# 1-wire_board.net
KiCad netlist of a schematic drawn in EAGLE
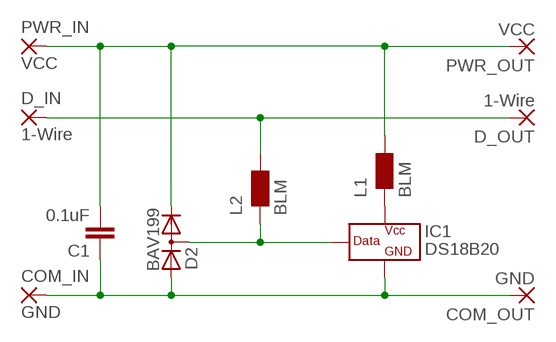
[diagram p0: schematic, sheet 1]

(export (version "E")
  (design (tool "Eeschema 10.0.6"))
  (components
    (comp (ref "C1")
      (value "0.1uF")
      (footprint "eagle-import:0805")
      (libsource (lib "eagle-import") (part "CAP0805"))
    )
    (comp (ref "COM_IN")
      (value "GND")
      (footprint "eagle-import:SMD2,54-5,08")
      (libsource (lib "eagle-import") (part "SMD5"))
    )
    (comp (ref "COM_OUT")
      (value "GND")
      (footprint "eagle-import:SMD2,54-5,08")
      (libsource (lib "eagle-import") (part "SMD5"))
    )
    (comp (ref "D2")
      (value "BAV199")
      (footprint "eagle-import:SOT23")
      (libsource (lib "eagle-import") (part "BAV199"))
    )
    (comp (ref "D_IN")
      (value "1-Wire")
      (footprint "eagle-import:SMD2,54-5,08")
      (libsource (lib "eagle-import") (part "SMD5"))
    )
    (comp (ref "D_OUT")
      (value "1-Wire")
      (footprint "eagle-import:SMD2,54-5,08")
      (libsource (lib "eagle-import") (part "SMD5"))
    )
    (comp (ref "IC1")
      (value "DS18B20")
      (footprint "eagle-import:TO92-")
      (libsource (lib "eagle-import") (part "DS18B20"))
    )
    (comp (ref "L1")
      (value "BLM")
      (footprint "eagle-import:0805")
      (libsource (lib "eagle-import") (part "WE-KIHQWE-KI_0805"))
    )
    (comp (ref "L2")
      (value "BLM")
      (footprint "eagle-import:0805")
      (libsource (lib "eagle-import") (part "WE-KIHQWE-KI_0805"))
    )
    (comp (ref "PWR_IN")
      (value "VCC")
      (footprint "eagle-import:SMD2,54-5,08")
      (libsource (lib "eagle-import") (part "SMD5"))
    )
    (comp (ref "PWR_OUT")
      (value "VCC")
      (footprint "eagle-import:SMD2,54-5,08")
      (libsource (lib "eagle-import") (part "SMD5"))
    )
  )
  (nets
    (net (code "1") (name "Net-(COM_IN-P)") (class "Default")
      (node (ref "C1") (pin "1") (pinfunction "1_1") (pintype "passive"))
      (node (ref "COM_IN") (pin "1") (pinfunction "P_1") (pintype "passive"))
      (node (ref "COM_OUT") (pin "1") (pinfunction "P_1") (pintype "passive"))
      (node (ref "D2") (pin "1") (pinfunction "A_1") (pintype "passive"))
      (node (ref "IC1") (pin "1") (pinfunction "GND_1") (pintype "bidirectional"))
    )
    (net (code "2") (name "Net-(D2-AC)") (class "Default")
      (node (ref "D2") (pin "3") (pinfunction "AC_3") (pintype "passive"))
      (node (ref "IC1") (pin "2") (pinfunction "DATA_2") (pintype "bidirectional"))
      (node (ref "L2") (pin "1") (pinfunction "1_1") (pintype "passive"))
    )
    (net (code "3") (name "Net-(D2-C)") (class "Default")
      (node (ref "C1") (pin "2") (pinfunction "2_2") (pintype "passive"))
      (node (ref "D2") (pin "2") (pinfunction "C_2") (pintype "passive"))
      (node (ref "L1") (pin "2") (pinfunction "2_2") (pintype "passive"))
      (node (ref "PWR_IN") (pin "1") (pinfunction "P_1") (pintype "passive"))
      (node (ref "PWR_OUT") (pin "1") (pinfunction "P_1") (pintype "passive"))
    )
    (net (code "4") (name "Net-(D_IN-P)") (class "Default")
      (node (ref "D_IN") (pin "1") (pinfunction "P_1") (pintype "passive"))
      (node (ref "D_OUT") (pin "1") (pinfunction "P_1") (pintype "passive"))
      (node (ref "L2") (pin "2") (pinfunction "2_2") (pintype "passive"))
    )
    (net (code "5") (name "Net-(IC1-VCC)") (class "Default")
      (node (ref "IC1") (pin "3") (pinfunction "VCC_3") (pintype "bidirectional"))
      (node (ref "L1") (pin "1") (pinfunction "1_1") (pintype "passive"))
    )
  )
)
